# Radio.net
KiCad netlist of a schematic drawn in Altium Designer
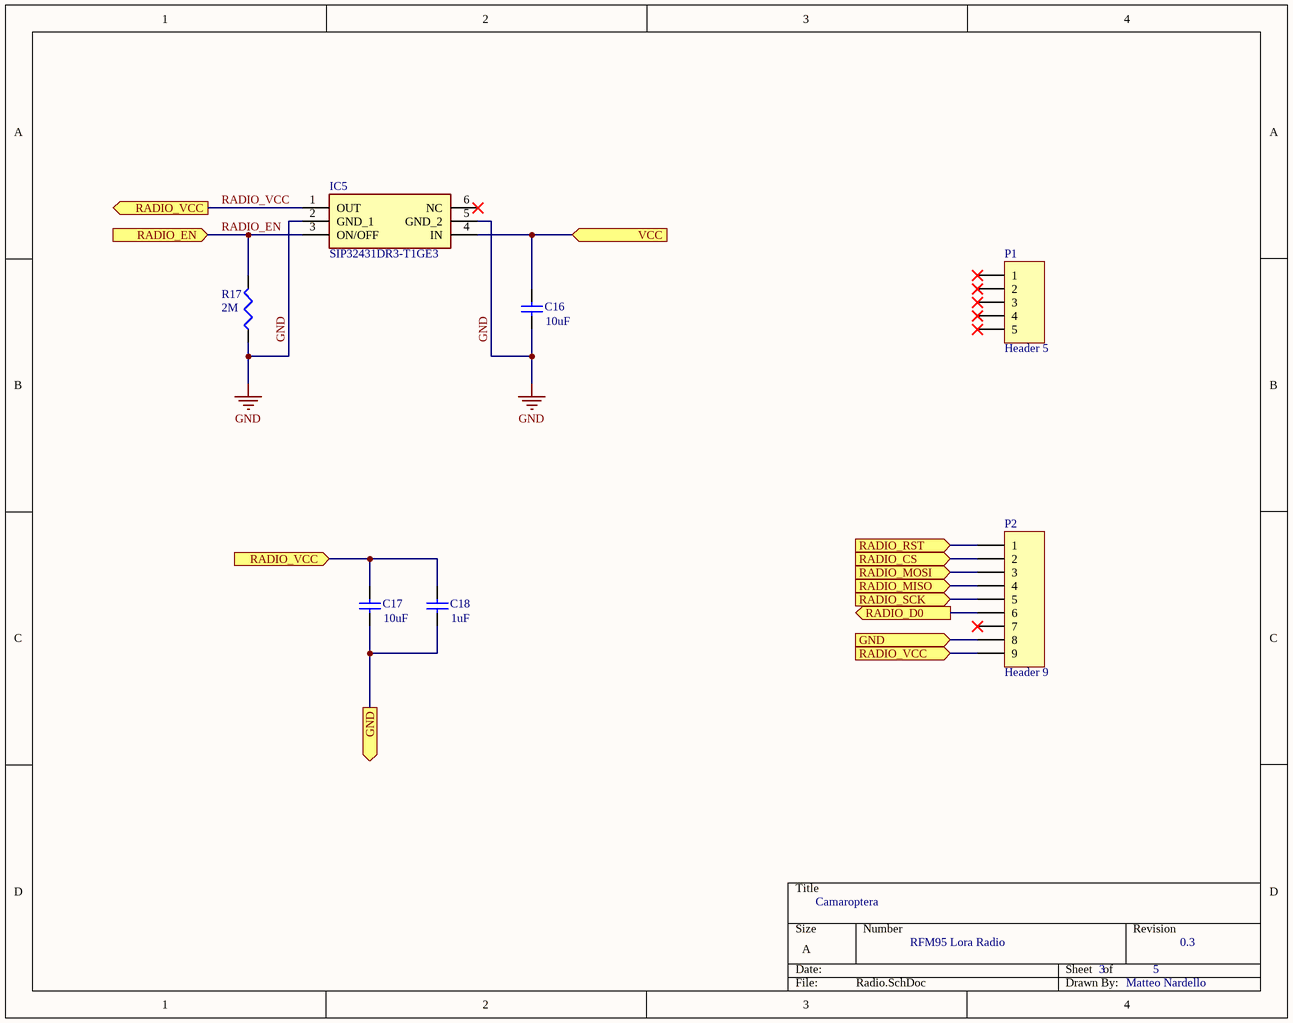
[diagram p0: Radio.SchDoc]

(export (version "E")
  (design (tool "Eeschema 10.0.6"))
  (components
    (comp (ref "C16")
      (value "10uF")
      (footprint "1608[0603]")
      (description "CAP CER 6.3V X5R/X7R 0603")
      (fields (field (name "Comment") "Cap") (field (name "PUBLISHER") "Altium Limited"))
      (libsource (lib "Miscellaneous Devices") (part "Cap"))
    )
    (comp (ref "C17")
      (value "10uF")
      (footprint "1608[0603]")
      (description "CAP CER 6.3V X5R/X7R 0603")
      (fields (field (name "Comment") "Cap") (field (name "PUBLISHER") "Altium Limited"))
      (libsource (lib "Miscellaneous Devices") (part "Cap"))
    )
    (comp (ref "C18")
      (value "1uF")
      (footprint "1608[0603]")
      (description "CAP CER 6.3V X5R/X7R 0603")
      (fields (field (name "Comment") "Cap") (field (name "PUBLISHER") "Altium Limited"))
      (libsource (lib "Miscellaneous Devices") (part "Cap"))
    )
    (comp (ref "IC5")
      (value "SIP32431DR3-T1GE3")
      (footprint "SamacSys:SOT65P210X110-6N")
      (description "10 pA, Ultra Low Leakage and Quiescent Current,\r\nLoad Switch with Reverse Blocking")
      (fields (field (name "MOUSER PART NUMBER") "781-SIP32431DR3-GE3"))
      (libsource (lib "*") (part "SIP32431DR3-T1GE3"))
    )
    (comp (ref "P1")
      (value "Header 5")
      (footprint "HDR1X5")
      (description "Header, 5-Pin")
      (fields (field (name "PUBLISHER") "Altium Limited"))
      (libsource (lib "Miscellaneous Connectors") (part "Header 5"))
    )
    (comp (ref "P2")
      (value "Header 9")
      (footprint "HDR1X9")
      (description "Header, 9-Pin")
      (fields (field (name "PUBLISHER") "Altium Limited"))
      (libsource (lib "Miscellaneous Connectors") (part "Header 9"))
    )
    (comp (ref "R17")
      (value "2M")
      (footprint "J1-0603")
      (description "RES 1/10W 1% 0603 SMD")
      (fields (field (name "Comment") "Res3") (field (name "PUBLISHER") "Altium Limited"))
      (libsource (lib "Miscellaneous Devices") (part "Res3"))
    )
  )
  (nets
    (net (code "1") (name "/RADIO_CS") (class "Default")
      (node (ref "P2") (pin "2") (pinfunction "2_2") (pintype "passive"))
    )
    (net (code "2") (name "/RADIO_D0") (class "Default")
      (node (ref "P2") (pin "6") (pinfunction "6_6") (pintype "passive"))
    )
    (net (code "3") (name "/RADIO_EN") (class "Default")
      (node (ref "IC5") (pin "3") (pinfunction "ON/OFF_3") (pintype "passive"))
      (node (ref "R17") (pin "2") (pinfunction "2_2") (pintype "passive"))
    )
    (net (code "4") (name "/RADIO_MISO") (class "Default")
      (node (ref "P2") (pin "4") (pinfunction "4_4") (pintype "passive"))
    )
    (net (code "5") (name "/RADIO_MOSI") (class "Default")
      (node (ref "P2") (pin "3") (pinfunction "3_3") (pintype "passive"))
    )
    (net (code "6") (name "/RADIO_RST") (class "Default")
      (node (ref "P2") (pin "1") (pinfunction "1_1") (pintype "passive"))
    )
    (net (code "7") (name "/RADIO_SCK") (class "Default")
      (node (ref "P2") (pin "5") (pinfunction "5_5") (pintype "passive"))
    )
    (net (code "8") (name "/RADIO_VCC") (class "Default")
      (node (ref "C17") (pin "2") (pinfunction "2_2") (pintype "passive"))
      (node (ref "C18") (pin "2") (pinfunction "2_2") (pintype "passive"))
      (node (ref "IC5") (pin "1") (pinfunction "OUT_1") (pintype "passive"))
      (node (ref "P2") (pin "9") (pinfunction "9_9") (pintype "passive"))
    )
    (net (code "9") (name "/VCC") (class "Default")
      (node (ref "C16") (pin "2") (pinfunction "2_2") (pintype "passive"))
      (node (ref "IC5") (pin "4") (pinfunction "IN_4") (pintype "passive"))
    )
    (net (code "10") (name "GND") (class "Default")
      (node (ref "C16") (pin "1") (pinfunction "1_1") (pintype "passive"))
      (node (ref "C17") (pin "1") (pinfunction "1_1") (pintype "passive"))
      (node (ref "C18") (pin "1") (pinfunction "1_1") (pintype "passive"))
      (node (ref "IC5") (pin "2") (pinfunction "GND_1_2") (pintype "passive"))
      (node (ref "IC5") (pin "5") (pinfunction "GND_2_5") (pintype "passive"))
      (node (ref "P2") (pin "8") (pinfunction "8_8") (pintype "passive"))
      (node (ref "R17") (pin "1") (pinfunction "1_1") (pintype "passive"))
    )
    (net (code "11") (name "unconnected-(IC5-NC-Pad6)") (class "Default")
      (node (ref "IC5") (pin "6") (pinfunction "NC_6") (pintype "passive+no_connect"))
    )
    (net (code "12") (name "unconnected-(P1-Pad1)") (class "Default")
      (node (ref "P1") (pin "1") (pinfunction "1_1") (pintype "passive+no_connect"))
    )
    (net (code "13") (name "unconnected-(P1-Pad2)") (class "Default")
      (node (ref "P1") (pin "2") (pinfunction "2_2") (pintype "passive+no_connect"))
    )
    (net (code "14") (name "unconnected-(P1-Pad3)") (class "Default")
      (node (ref "P1") (pin "3") (pinfunction "3_3") (pintype "passive+no_connect"))
    )
    (net (code "15") (name "unconnected-(P1-Pad4)") (class "Default")
      (node (ref "P1") (pin "4") (pinfunction "4_4") (pintype "passive+no_connect"))
    )
    (net (code "16") (name "unconnected-(P1-Pad5)") (class "Default")
      (node (ref "P1") (pin "5") (pinfunction "5_5") (pintype "passive+no_connect"))
    )
    (net (code "17") (name "unconnected-(P2-Pad7)") (class "Default")
      (node (ref "P2") (pin "7") (pinfunction "7_7") (pintype "passive+no_connect"))
    )
  )
)
